# SSOP-TSSOP8.net
KiCad netlist of a schematic drawn in Altium Designer
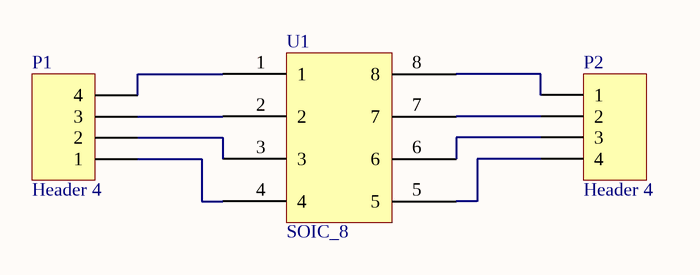
[diagram p0: SSOP-TSSOP8.SchDoc]

(export (version "E")
  (design (tool "Eeschema 10.0.6"))
  (components
    (comp (ref "P1")
      (value "Header 4")
      (footprint "HDR1X4")
      (description "Header, 4-Pin")
      (fields (field (name "PUBLISHER") "Altium Limited"))
      (libsource (lib "Miscellaneous Connectors") (part "Header 4"))
    )
    (comp (ref "P2")
      (value "Header 4")
      (footprint "HDR1X4")
      (description "Header, 4-Pin")
      (fields (field (name "PUBLISHER") "Altium Limited"))
      (libsource (lib "") (part "Header 4_1"))
    )
    (comp (ref "U1")
      (value "SOIC_8")
      (footprint "SOIC8")
      (libsource (lib "PCB_Breakout_Boards") (part "SOIC_8"))
    )
  )
  (nets
    (net (code "1") (name "Net-(P1-Pad1)") (class "Default")
      (node (ref "P1") (pin "1") (pinfunction "1_1") (pintype "passive"))
      (node (ref "U1") (pin "4") (pinfunction "4_4") (pintype "passive"))
    )
    (net (code "2") (name "Net-(P1-Pad2)") (class "Default")
      (node (ref "P1") (pin "2") (pinfunction "2_2") (pintype "passive"))
      (node (ref "U1") (pin "3") (pinfunction "3_3") (pintype "passive"))
    )
    (net (code "3") (name "Net-(P1-Pad3)") (class "Default")
      (node (ref "P1") (pin "3") (pinfunction "3_3") (pintype "passive"))
      (node (ref "U1") (pin "2") (pinfunction "2_2") (pintype "passive"))
    )
    (net (code "4") (name "Net-(P1-Pad4)") (class "Default")
      (node (ref "P1") (pin "4") (pinfunction "4_4") (pintype "passive"))
      (node (ref "U1") (pin "1") (pinfunction "1_1") (pintype "passive"))
    )
    (net (code "5") (name "Net-(P2-Pad1)") (class "Default")
      (node (ref "P2") (pin "1") (pinfunction "1_1") (pintype "passive"))
      (node (ref "U1") (pin "8") (pinfunction "8_8") (pintype "passive"))
    )
    (net (code "6") (name "Net-(P2-Pad2)") (class "Default")
      (node (ref "P2") (pin "2") (pinfunction "2_2") (pintype "passive"))
      (node (ref "U1") (pin "7") (pinfunction "7_7") (pintype "passive"))
    )
    (net (code "7") (name "Net-(P2-Pad3)") (class "Default")
      (node (ref "P2") (pin "3") (pinfunction "3_3") (pintype "passive"))
      (node (ref "U1") (pin "6") (pinfunction "6_6") (pintype "passive"))
    )
    (net (code "8") (name "Net-(P2-Pad4)") (class "Default")
      (node (ref "P2") (pin "4") (pinfunction "4_4") (pintype "passive"))
      (node (ref "U1") (pin "5") (pinfunction "5_5") (pintype "passive"))
    )
  )
)
